# H-Bridge.net
KiCad netlist of a schematic drawn in Altium Designer
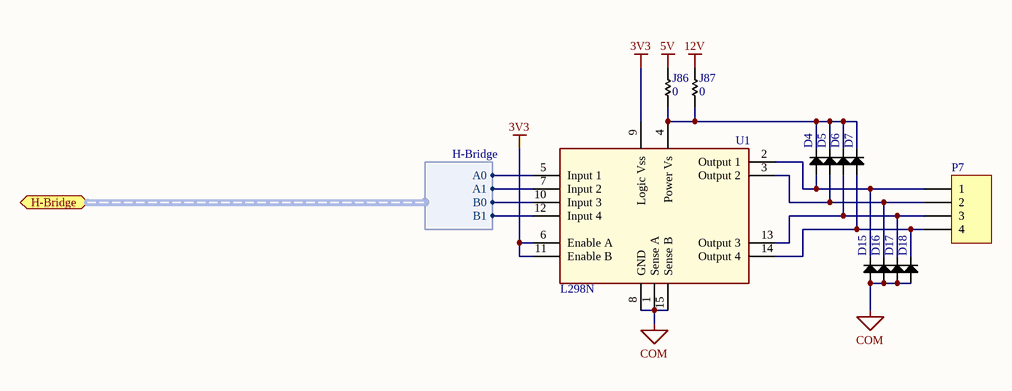
[diagram p0: H-Bridge.SchDoc]

(export (version "E")
  (design (tool "Eeschema 10.0.6"))
  (components
    (comp (ref "D4")
      (value "Diode")
      (footprint "DOS-214AC (SMA)")
      (description "DIODE GEN PURPOSE 1000V 1A SMA")
      (fields
        (field (name "PART NUMBER") "S1M-13-F")
        (field (name "MANUFACTURER") "Diodes Inc.")
        (field (name "CREATED BY") "Pier-Yves")
      )
      (libsource (lib "local") (part "Diode"))
    )
    (comp (ref "D5")
      (value "Diode")
      (footprint "DOS-214AC (SMA)")
      (description "DIODE GEN PURPOSE 1000V 1A SMA")
      (fields
        (field (name "PART NUMBER") "S1M-13-F")
        (field (name "MANUFACTURER") "Diodes Inc.")
        (field (name "CREATED BY") "Pier-Yves")
      )
      (libsource (lib "local") (part "Diode"))
    )
    (comp (ref "D6")
      (value "Diode")
      (footprint "DOS-214AC (SMA)")
      (description "DIODE GEN PURPOSE 1000V 1A SMA")
      (fields
        (field (name "PART NUMBER") "S1M-13-F")
        (field (name "MANUFACTURER") "Diodes Inc.")
        (field (name "CREATED BY") "Pier-Yves")
      )
      (libsource (lib "local") (part "Diode"))
    )
    (comp (ref "D7")
      (value "Diode")
      (footprint "DOS-214AC (SMA)")
      (description "DIODE GEN PURPOSE 1000V 1A SMA")
      (fields
        (field (name "PART NUMBER") "S1M-13-F")
        (field (name "MANUFACTURER") "Diodes Inc.")
        (field (name "CREATED BY") "Pier-Yves")
      )
      (libsource (lib "local") (part "Diode"))
    )
    (comp (ref "D15")
      (value "Diode")
      (footprint "DOS-214AC (SMA)")
      (description "DIODE GEN PURPOSE 1000V 1A SMA")
      (fields
        (field (name "PART NUMBER") "S1M-13-F")
        (field (name "MANUFACTURER") "Diodes Inc.")
        (field (name "CREATED BY") "Pier-Yves")
      )
      (libsource (lib "local") (part "Diode"))
    )
    (comp (ref "D16")
      (value "Diode")
      (footprint "DOS-214AC (SMA)")
      (description "DIODE GEN PURPOSE 1000V 1A SMA")
      (fields
        (field (name "PART NUMBER") "S1M-13-F")
        (field (name "MANUFACTURER") "Diodes Inc.")
        (field (name "CREATED BY") "Pier-Yves")
      )
      (libsource (lib "local") (part "Diode"))
    )
    (comp (ref "D17")
      (value "Diode")
      (footprint "DOS-214AC (SMA)")
      (description "DIODE GEN PURPOSE 1000V 1A SMA")
      (fields
        (field (name "PART NUMBER") "S1M-13-F")
        (field (name "MANUFACTURER") "Diodes Inc.")
        (field (name "CREATED BY") "Pier-Yves")
      )
      (libsource (lib "local") (part "Diode"))
    )
    (comp (ref "D18")
      (value "Diode")
      (footprint "DOS-214AC (SMA)")
      (description "DIODE GEN PURPOSE 1000V 1A SMA")
      (fields
        (field (name "PART NUMBER") "S1M-13-F")
        (field (name "MANUFACTURER") "Diodes Inc.")
        (field (name "CREATED BY") "Pier-Yves")
      )
      (libsource (lib "local") (part "Diode"))
    )
    (comp (ref "J86")
      (value "0")
      (footprint "0805 - Resistor")
      (description "RES 0.0 OHM 1/8W JUMP 0805")
      (fields
        (field (name "PART NUMBER") "Jumper-0805")
        (field (name "MANUFACTURER") "Stackpole electronic")
        (field (name "CREATED BY") "Pier-Yves")
      )
      (libsource (lib "local") (part "Res"))
    )
    (comp (ref "J87")
      (value "0")
      (footprint "0805 - Resistor")
      (description "RES 0.0 OHM 1/8W JUMP 0805")
      (fields
        (field (name "PART NUMBER") "Jumper-0805")
        (field (name "MANUFACTURER") "Stackpole electronic")
        (field (name "CREATED BY") "Pier-Yves")
      )
      (libsource (lib "local") (part "Res"))
    )
    (comp (ref "P7")
      (value "Header 1X4")
      (footprint "Headers - 1x4 - Vertical - Lock")
      (description "CONN HEADER 4POS .100\" STR TIN")
      (fields
        (field (name "PART NUMBER") "Header-0.100-Vertical-Lock-1X4")
        (field (name "MANUFACTURER") "Molex Inc")
        (field (name "PUBLISHER") "Altium Limited")
        (field (name "CREATED BY") "Pier-Yves")
      )
      (libsource (lib "local") (part "Header 1X4"))
    )
    (comp (ref "U1")
      (value "L298N")
      (footprint "Multiwatt_15")
      (description "IC BRIDGE DRIVER PAR 15MULTIWATT")
      (fields
        (field (name "MANUFACTURER") "STMicroelectronics")
        (field (name "POWER") "25")
        (field (name "CREATED BY") "Pier-Yves")
      )
      (libsource (lib "local") (part "L298N"))
    )
  )
  (nets
    (net (code "2") (name "/A0") (class "Default")
      (node (ref "U1") (pin "5") (pinfunction "Input_1_5") (pintype "passive"))
    )
    (net (code "3") (name "/A1") (class "Default")
      (node (ref "U1") (pin "7") (pinfunction "Input_2_7") (pintype "passive"))
    )
    (net (code "4") (name "/B0") (class "Default")
      (node (ref "U1") (pin "10") (pinfunction "Input_3_10") (pintype "passive"))
    )
    (net (code "5") (name "/B1") (class "Default")
      (node (ref "U1") (pin "12") (pinfunction "Input_4_12") (pintype "passive"))
    )
    (net (code "7") (name "3V3") (class "Default")
      (node (ref "U1") (pin "11") (pinfunction "Enable_B_11") (pintype "passive"))
      (node (ref "U1") (pin "6") (pinfunction "Enable_A_6") (pintype "passive"))
      (node (ref "U1") (pin "9") (pinfunction "Logic_Vss_9") (pintype "passive"))
    )
    (net (code "8") (name "5V") (class "Default")
      (node (ref "J86") (pin "2") (pinfunction "2_2") (pintype "passive"))
    )
    (net (code "9") (name "12V") (class "Default")
      (node (ref "J87") (pin "2") (pinfunction "2_2") (pintype "passive"))
    )
    (net (code "10") (name "COM") (class "Default")
      (node (ref "D15") (pin "1") (pinfunction "A_1") (pintype "passive"))
      (node (ref "D16") (pin "1") (pinfunction "A_1") (pintype "passive"))
      (node (ref "D17") (pin "1") (pinfunction "A_1") (pintype "passive"))
      (node (ref "D18") (pin "1") (pinfunction "A_1") (pintype "passive"))
      (node (ref "U1") (pin "1") (pinfunction "Sense_A_1") (pintype "passive"))
      (node (ref "U1") (pin "15") (pinfunction "Sense_B_15") (pintype "passive"))
      (node (ref "U1") (pin "8") (pinfunction "GND_8") (pintype "passive"))
    )
    (net (code "11") (name "Net-(D4-K)") (class "Default")
      (node (ref "D4") (pin "2") (pinfunction "K_2") (pintype "passive"))
      (node (ref "D5") (pin "2") (pinfunction "K_2") (pintype "passive"))
      (node (ref "D6") (pin "2") (pinfunction "K_2") (pintype "passive"))
      (node (ref "D7") (pin "2") (pinfunction "K_2") (pintype "passive"))
      (node (ref "J86") (pin "1") (pinfunction "1_1") (pintype "passive"))
      (node (ref "J87") (pin "1") (pinfunction "1_1") (pintype "passive"))
      (node (ref "U1") (pin "4") (pinfunction "Power_Vs_4") (pintype "passive"))
    )
    (net (code "12") (name "Net-(D15-K)") (class "Default")
      (node (ref "D15") (pin "2") (pinfunction "K_2") (pintype "passive"))
      (node (ref "D4") (pin "1") (pinfunction "A_1") (pintype "passive"))
      (node (ref "P7") (pin "1") (pinfunction "1_1") (pintype "passive"))
      (node (ref "U1") (pin "2") (pinfunction "Output_1_2") (pintype "passive"))
    )
    (net (code "13") (name "Net-(D16-K)") (class "Default")
      (node (ref "D16") (pin "2") (pinfunction "K_2") (pintype "passive"))
      (node (ref "D5") (pin "1") (pinfunction "A_1") (pintype "passive"))
      (node (ref "P7") (pin "2") (pinfunction "2_2") (pintype "passive"))
      (node (ref "U1") (pin "3") (pinfunction "Output_2_3") (pintype "passive"))
    )
    (net (code "14") (name "Net-(D17-K)") (class "Default")
      (node (ref "D17") (pin "2") (pinfunction "K_2") (pintype "passive"))
      (node (ref "D6") (pin "1") (pinfunction "A_1") (pintype "passive"))
      (node (ref "P7") (pin "3") (pinfunction "3_3") (pintype "passive"))
      (node (ref "U1") (pin "13") (pinfunction "Output_3_13") (pintype "passive"))
    )
    (net (code "15") (name "Net-(D18-K)") (class "Default")
      (node (ref "D18") (pin "2") (pinfunction "K_2") (pintype "passive"))
      (node (ref "D7") (pin "1") (pinfunction "A_1") (pintype "passive"))
      (node (ref "P7") (pin "4") (pinfunction "4_4") (pintype "passive"))
      (node (ref "U1") (pin "14") (pinfunction "Output_4_14") (pintype "passive"))
    )
  )
)
